# RPi.net
KiCad netlist of a schematic drawn in Altium Designer
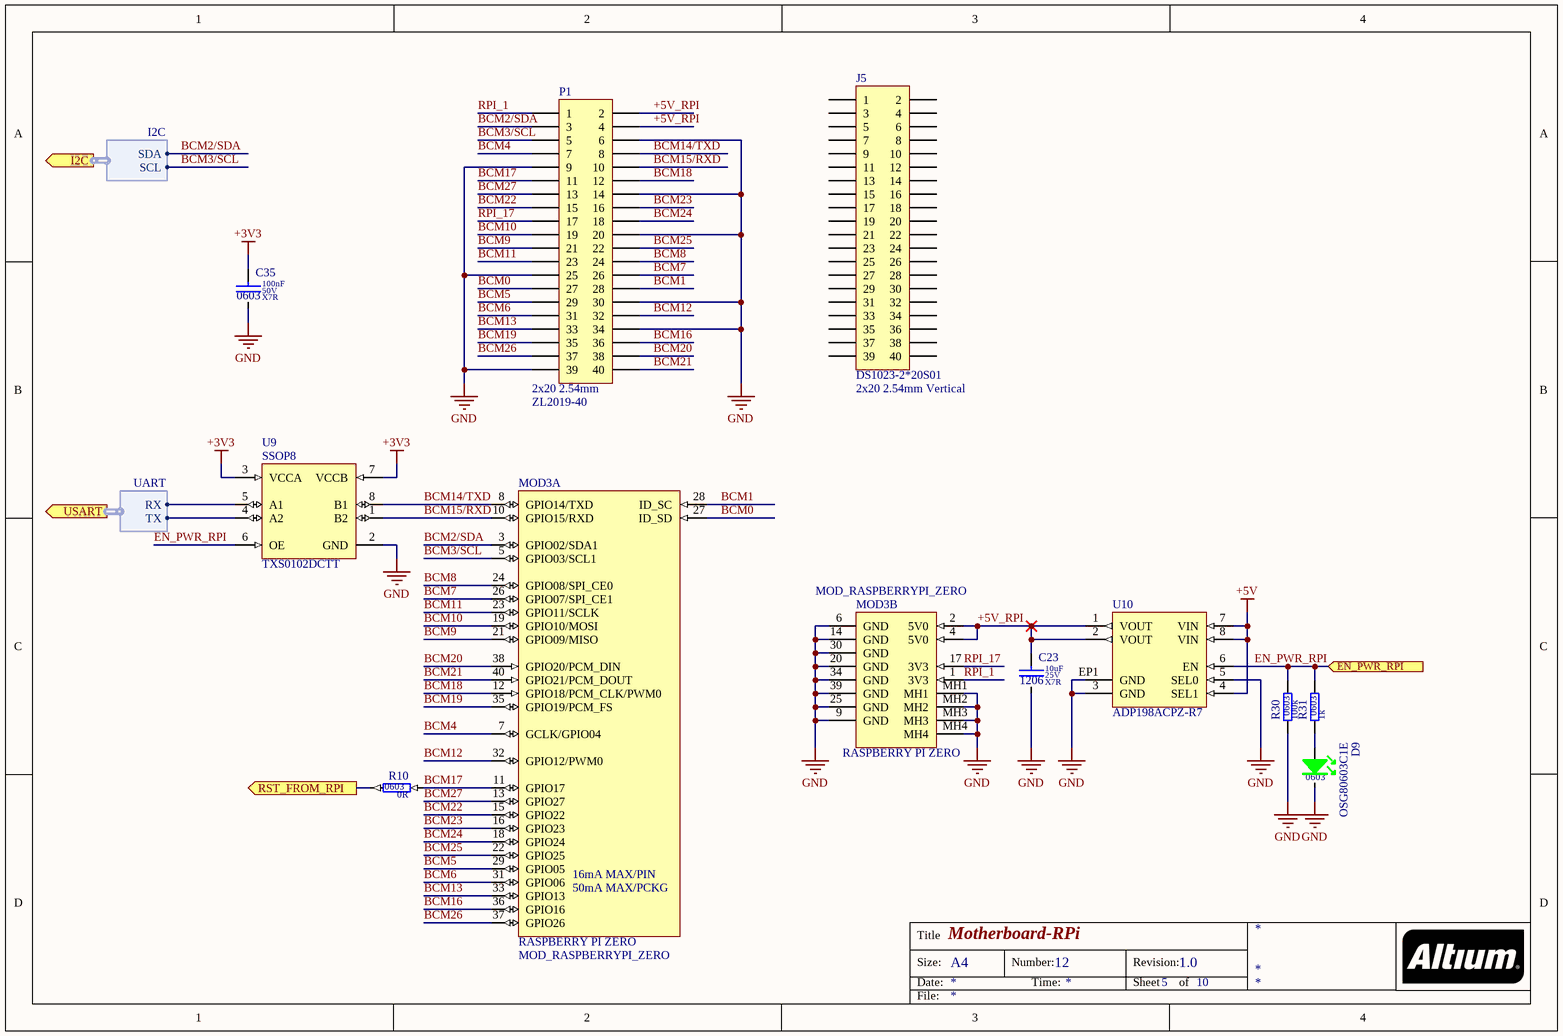
[diagram p0: RPi.SchDoc]

(export (version "E")
  (design (tool "Eeschema 10.0.6"))
  (components
    (comp (ref "C23")
      (value "10uF")
      (footprint "C_1206_3216")
      (description "Capacitor")
      (fields
        (field (name "DIELECTRIC") "X7R")
        (field (name "VOLTAGE") "25V")
        (field (name "SCH_FOOTPRINT") "1206")
        (field (name "PART NUMBER") "C_10uF_25V_X7R_1206_10")
        (field (name "MANUFACTURER") "Samsung Electro-Mechanics")
      )
      (libsource (lib "Library") (part "C"))
    )
    (comp (ref "C35")
      (value "100nF")
      (footprint "C_0603_1608")
      (description "Capacitor")
      (fields
        (field (name "DIELECTRIC") "X7R")
        (field (name "VOLTAGE") "50V")
        (field (name "SCH_FOOTPRINT") "0603")
        (field (name "PART NUMBER") "C_100nF_50V_X7R_0603_5")
        (field (name "MANUFACTURER") "Samsung")
      )
      (libsource (lib "Library") (part "C"))
    )
    (comp (ref "D9")
      (value "OSG80603C1E")
      (footprint "OL_0603_1608")
      (description "LED GREEN")
      (fields
        (field (name "SCH_FOOTPRINT") "0603")
        (field (name "PART NUMBER") "OL_G_0603_OSG80603C1E")
        (field (name "MANUFACTURER") "Optosupply")
      )
      (libsource (lib "Library") (part "OL_G"))
    )
    (comp (ref "J5")
      (value "DS1023-2*20S01")
      (footprint "J_HEADER_2x20_2.54_VERTICAL")
      (description "Pin Header")
      (fields
        (field (name "PART NUMBER") "J_HEADER_2x20_2.54_VERTICAL")
        (field (name "SCH_FOOTPRINT") "2x20 2.54mm Vertical")
        (field (name "MANUFACTURER") "Connfly")
      )
      (libsource (lib "Library") (part "J_HEADER_2x20"))
    )
    (comp (ref "MOD3")
      (value "RASPBERRY PI ZERO")
      (footprint "MOD_RASPBERRYPI_ZERO")
      (fields
        (field (name "PART NUMBER") "MOD_RASPBERRYPI_ZERO")
        (field (name "SCH_FOOTPRINT") "MOD_RASPBERRYPI_ZERO")
        (field (name "MANUFACTURER") "Raspberry Pi")
      )
      (libsource (lib "Library") (part "MOD_RASPBERRYPI_3B"))
    )
    (comp (ref "P1")
      (value "ZL2019-40")
      (footprint "P_HEADER_2x20_2.54_HIGH")
      (description "Pin Header")
      (fields
        (field (name "SCH_FOOTPRINT") "2x20 2.54mm")
        (field (name "PART NUMBER") "P_HEADER_2x20_2.54_HIGH")
        (field (name "MANUFACTURER") "Ninigi")
      )
      (libsource (lib "Library") (part "P_HEADER_2x20"))
    )
    (comp (ref "R10")
      (value "0R")
      (footprint "R_0603_1608")
      (fields
        (field (name "SCH_FOOTPRINT") "0603")
        (field (name "PART NUMBER") "R_0R_0603_5")
        (field (name "VOLTAGE") "50V")
        (field (name "POWER") "100mW")
      )
      (libsource (lib "") (part "R_1"))
    )
    (comp (ref "R30")
      (value "100k")
      (footprint "R_0603_1608")
      (fields
        (field (name "SCH_FOOTPRINT") "0603")
        (field (name "PART NUMBER") "R_100k_0603_1")
        (field (name "VOLTAGE") "50V")
        (field (name "POWER") "100mW")
      )
      (libsource (lib "Library") (part "R"))
    )
    (comp (ref "R31")
      (value "1k")
      (footprint "R_0603_1608")
      (fields
        (field (name "SCH_FOOTPRINT") "0603")
        (field (name "PART NUMBER") "R_1k_0603_1")
        (field (name "VOLTAGE") "75V")
        (field (name "POWER") "100mW")
      )
      (libsource (lib "Library") (part "R"))
    )
    (comp (ref "U9")
      (value "TXS0102DCTT")
      (footprint "SSOP8_3x3")
      (fields
        (field (name "SCH_FOOTPRINT") "SSOP8")
        (field (name "PART NUMBER") "U_TXS0102DCTT")
        (field (name "MANUFACTURER") "Texas Instruments")
      )
      (libsource (lib "Library") (part "U_TXS0102_DCT_DCU"))
    )
    (comp (ref "U10")
      (value "ADP198ACPZ-R7")
      (footprint "LFCSP-8-10")
      (fields
        (field (name "SCH_FOOTPRINT") "LFCSP8")
        (field (name "PART NUMBER") "U_ADP198ACPZ-R7")
        (field (name "MANUFACTURER") "Analog Devices")
        (field (name "Comment") "high-side load switch")
      )
      (libsource (lib "Library") (part "U_ADP198ACPZ-R7"))
    )
  )
  (nets
    (net (code "3") (name "+3V3") (class "Default")
      (node (ref "C35") (pin "1") (pinfunction "1_1") (pintype "passive"))
      (node (ref "U9") (pin "3") (pinfunction "VCCA_3") (pintype "input"))
      (node (ref "U9") (pin "7") (pinfunction "VCCB_7") (pintype "input"))
    )
    (net (code "4") (name "+5V") (class "Default")
      (node (ref "U10") (pin "4") (pinfunction "SEL1_4") (pintype "input"))
      (node (ref "U10") (pin "7") (pinfunction "VIN_7") (pintype "input"))
      (node (ref "U10") (pin "8") (pinfunction "VIN_8") (pintype "input"))
    )
    (net (code "5") (name "/+5V_RPI") (class "Default")
      (node (ref "C23") (pin "1") (pinfunction "1_1") (pintype "passive"))
      (node (ref "MOD3") (pin "2") (pinfunction "5V0_2") (pintype "input"))
      (node (ref "MOD3") (pin "4") (pinfunction "5V0_4") (pintype "input"))
      (node (ref "P1") (pin "2") (pinfunction "2_2") (pintype "passive"))
      (node (ref "P1") (pin "4") (pinfunction "4_4") (pintype "passive"))
      (node (ref "U10") (pin "1") (pinfunction "VOUT_1") (pintype "output"))
      (node (ref "U10") (pin "2") (pinfunction "VOUT_2") (pintype "output"))
    )
    (net (code "6") (name "/BCM0") (class "Default")
      (node (ref "MOD3") (pin "27") (pinfunction "ID_SD_27") (pintype "input"))
      (node (ref "P1") (pin "27") (pinfunction "27_27") (pintype "passive"))
    )
    (net (code "7") (name "/BCM1") (class "Default")
      (node (ref "MOD3") (pin "28") (pinfunction "ID_SC_28") (pintype "input"))
      (node (ref "P1") (pin "28") (pinfunction "28_28") (pintype "passive"))
    )
    (net (code "8") (name "/BCM2{slash}SDA") (class "Default")
      (node (ref "MOD3") (pin "3") (pinfunction "GPIO02/SDA1_3") (pintype "bidirectional"))
      (node (ref "P1") (pin "3") (pinfunction "3_3") (pintype "passive"))
    )
    (net (code "9") (name "/BCM3{slash}SCL") (class "Default")
      (node (ref "MOD3") (pin "5") (pinfunction "GPIO03/SCL1_5") (pintype "bidirectional"))
      (node (ref "P1") (pin "5") (pinfunction "5_5") (pintype "passive"))
    )
    (net (code "10") (name "/BCM4") (class "Default")
      (node (ref "MOD3") (pin "7") (pinfunction "GCLK/GPIO04_7") (pintype "bidirectional"))
      (node (ref "P1") (pin "7") (pinfunction "7_7") (pintype "passive"))
    )
    (net (code "11") (name "/BCM5") (class "Default")
      (node (ref "MOD3") (pin "29") (pinfunction "GPIO05_29") (pintype "bidirectional"))
      (node (ref "P1") (pin "29") (pinfunction "29_29") (pintype "passive"))
    )
    (net (code "12") (name "/BCM6") (class "Default")
      (node (ref "MOD3") (pin "31") (pinfunction "GPIO06_31") (pintype "bidirectional"))
      (node (ref "P1") (pin "31") (pinfunction "31_31") (pintype "passive"))
    )
    (net (code "13") (name "/BCM7") (class "Default")
      (node (ref "MOD3") (pin "26") (pinfunction "GPIO07/SPI_CE1_26") (pintype "bidirectional"))
      (node (ref "P1") (pin "26") (pinfunction "26_26") (pintype "passive"))
    )
    (net (code "14") (name "/BCM8") (class "Default")
      (node (ref "MOD3") (pin "24") (pinfunction "GPIO08/SPI_CE0_24") (pintype "bidirectional"))
      (node (ref "P1") (pin "24") (pinfunction "24_24") (pintype "passive"))
    )
    (net (code "15") (name "/BCM9") (class "Default")
      (node (ref "MOD3") (pin "21") (pinfunction "GPIO09/MISO_21") (pintype "bidirectional"))
      (node (ref "P1") (pin "21") (pinfunction "21_21") (pintype "passive"))
    )
    (net (code "16") (name "/BCM10") (class "Default")
      (node (ref "MOD3") (pin "19") (pinfunction "GPIO10/MOSI_19") (pintype "bidirectional"))
      (node (ref "P1") (pin "19") (pinfunction "19_19") (pintype "passive"))
    )
    (net (code "17") (name "/BCM11") (class "Default")
      (node (ref "MOD3") (pin "23") (pinfunction "GPIO11/SCLK_23") (pintype "bidirectional"))
      (node (ref "P1") (pin "23") (pinfunction "23_23") (pintype "passive"))
    )
    (net (code "18") (name "/BCM12") (class "Default")
      (node (ref "MOD3") (pin "32") (pinfunction "GPIO12/PWM0_32") (pintype "bidirectional"))
      (node (ref "P1") (pin "32") (pinfunction "32_32") (pintype "passive"))
    )
    (net (code "19") (name "/BCM13") (class "Default")
      (node (ref "MOD3") (pin "33") (pinfunction "GPIO13_33") (pintype "bidirectional"))
      (node (ref "P1") (pin "33") (pinfunction "33_33") (pintype "passive"))
    )
    (net (code "20") (name "/BCM14{slash}TXD") (class "Default")
      (node (ref "MOD3") (pin "8") (pinfunction "GPIO14/TXD_8") (pintype "bidirectional"))
      (node (ref "P1") (pin "8") (pinfunction "8_8") (pintype "passive"))
      (node (ref "U9") (pin "8") (pinfunction "B1_8") (pintype "bidirectional"))
    )
    (net (code "21") (name "/BCM15{slash}RXD") (class "Default")
      (node (ref "MOD3") (pin "10") (pinfunction "GPIO15/RXD_10") (pintype "bidirectional"))
      (node (ref "P1") (pin "10") (pinfunction "10_10") (pintype "passive"))
      (node (ref "U9") (pin "1") (pinfunction "B2_1") (pintype "bidirectional"))
    )
    (net (code "22") (name "/BCM16") (class "Default")
      (node (ref "MOD3") (pin "36") (pinfunction "GPIO16_36") (pintype "bidirectional"))
      (node (ref "P1") (pin "36") (pinfunction "36_36") (pintype "passive"))
    )
    (net (code "23") (name "/BCM17") (class "Default")
      (node (ref "MOD3") (pin "11") (pinfunction "GPIO17_11") (pintype "bidirectional"))
      (node (ref "P1") (pin "11") (pinfunction "11_11") (pintype "passive"))
      (node (ref "R10") (pin "1") (pinfunction "1_1") (pintype "input"))
    )
    (net (code "24") (name "/BCM18") (class "Default")
      (node (ref "MOD3") (pin "12") (pinfunction "GPIO18/PCM_CLK/PWM0_12") (pintype "input"))
      (node (ref "P1") (pin "12") (pinfunction "12_12") (pintype "passive"))
    )
    (net (code "25") (name "/BCM19") (class "Default")
      (node (ref "MOD3") (pin "35") (pinfunction "GPIO19/PCM_FS_35") (pintype "bidirectional"))
      (node (ref "P1") (pin "35") (pinfunction "35_35") (pintype "passive"))
    )
    (net (code "26") (name "/BCM20") (class "Default")
      (node (ref "MOD3") (pin "38") (pinfunction "GPIO20/PCM_DIN_38") (pintype "input"))
      (node (ref "P1") (pin "38") (pinfunction "38_38") (pintype "passive"))
    )
    (net (code "27") (name "/BCM21") (class "Default")
      (node (ref "MOD3") (pin "40") (pinfunction "GPIO21/PCM_DOUT_40") (pintype "input"))
      (node (ref "P1") (pin "40") (pinfunction "40_40") (pintype "passive"))
    )
    (net (code "28") (name "/BCM22") (class "Default")
      (node (ref "MOD3") (pin "15") (pinfunction "GPIO22_15") (pintype "bidirectional"))
      (node (ref "P1") (pin "15") (pinfunction "15_15") (pintype "passive"))
    )
    (net (code "29") (name "/BCM23") (class "Default")
      (node (ref "MOD3") (pin "16") (pinfunction "GPIO23_16") (pintype "bidirectional"))
      (node (ref "P1") (pin "16") (pinfunction "16_16") (pintype "passive"))
    )
    (net (code "30") (name "/BCM24") (class "Default")
      (node (ref "MOD3") (pin "18") (pinfunction "GPIO24_18") (pintype "bidirectional"))
      (node (ref "P1") (pin "18") (pinfunction "18_18") (pintype "passive"))
    )
    (net (code "31") (name "/BCM25") (class "Default")
      (node (ref "MOD3") (pin "22") (pinfunction "GPIO25_22") (pintype "bidirectional"))
      (node (ref "P1") (pin "22") (pinfunction "22_22") (pintype "passive"))
    )
    (net (code "32") (name "/BCM26") (class "Default")
      (node (ref "MOD3") (pin "37") (pinfunction "GPIO26_37") (pintype "bidirectional"))
      (node (ref "P1") (pin "37") (pinfunction "37_37") (pintype "passive"))
    )
    (net (code "33") (name "/BCM27") (class "Default")
      (node (ref "MOD3") (pin "13") (pinfunction "GPIO27_13") (pintype "bidirectional"))
      (node (ref "P1") (pin "13") (pinfunction "13_13") (pintype "passive"))
    )
    (net (code "34") (name "/EN_PWR_RPI") (class "Default")
      (node (ref "R30") (pin "2") (pinfunction "2_2") (pintype "passive"))
      (node (ref "R31") (pin "2") (pinfunction "2_2") (pintype "passive"))
      (node (ref "U10") (pin "6") (pinfunction "EN_6") (pintype "input"))
      (node (ref "U9") (pin "6") (pinfunction "OE_6") (pintype "input"))
    )
    (net (code "35") (name "/RPI_1") (class "Default")
      (node (ref "MOD3") (pin "1") (pinfunction "3V3_1") (pintype "input"))
      (node (ref "P1") (pin "1") (pinfunction "1_1") (pintype "passive"))
    )
    (net (code "36") (name "/RPI_17") (class "Default")
      (node (ref "MOD3") (pin "17") (pinfunction "3V3_17") (pintype "input"))
      (node (ref "P1") (pin "17") (pinfunction "17_17") (pintype "passive"))
    )
    (net (code "37") (name "/RST_FROM_RPI") (class "Default")
      (node (ref "R10") (pin "2") (pinfunction "2_2") (pintype "output"))
    )
    (net (code "38") (name "/RX") (class "Default")
      (node (ref "U9") (pin "5") (pinfunction "A1_5") (pintype "bidirectional"))
    )
    (net (code "39") (name "/TX") (class "Default")
      (node (ref "U9") (pin "4") (pinfunction "A2_4") (pintype "bidirectional"))
    )
    (net (code "42") (name "GND") (class "Default")
      (node (ref "C23") (pin "2") (pinfunction "2_2") (pintype "passive"))
      (node (ref "C35") (pin "2") (pinfunction "2_2") (pintype "passive"))
      (node (ref "D9") (pin "1") (pinfunction "K_1") (pintype "passive"))
      (node (ref "MOD3") (pin "14") (pinfunction "GND_14") (pintype "power_in"))
      (node (ref "MOD3") (pin "20") (pinfunction "GND_20") (pintype "power_in"))
      (node (ref "MOD3") (pin "25") (pinfunction "GND_25") (pintype "power_in"))
      (node (ref "MOD3") (pin "30") (pinfunction "GND_30") (pintype "power_in"))
      (node (ref "MOD3") (pin "34") (pinfunction "GND_34") (pintype "power_in"))
      (node (ref "MOD3") (pin "39") (pinfunction "GND_39") (pintype "power_in"))
      (node (ref "MOD3") (pin "6") (pinfunction "GND_6") (pintype "power_in"))
      (node (ref "MOD3") (pin "9") (pinfunction "GND_9") (pintype "power_in"))
      (node (ref "MOD3") (pin "MH1") (pinfunction "MH1_MH1") (pintype "passive"))
      (node (ref "MOD3") (pin "MH2") (pinfunction "MH2_MH2") (pintype "passive"))
      (node (ref "MOD3") (pin "MH3") (pinfunction "MH3_MH3") (pintype "passive"))
      (node (ref "MOD3") (pin "MH4") (pinfunction "MH4_MH4") (pintype "passive"))
      (node (ref "P1") (pin "14") (pinfunction "14_14") (pintype "passive"))
      (node (ref "P1") (pin "20") (pinfunction "20_20") (pintype "passive"))
      (node (ref "P1") (pin "25") (pinfunction "25_25") (pintype "passive"))
      (node (ref "P1") (pin "30") (pinfunction "30_30") (pintype "passive"))
      (node (ref "P1") (pin "34") (pinfunction "34_34") (pintype "passive"))
      (node (ref "P1") (pin "39") (pinfunction "39_39") (pintype "passive"))
      (node (ref "P1") (pin "6") (pinfunction "6_6") (pintype "passive"))
      (node (ref "P1") (pin "9") (pinfunction "9_9") (pintype "passive"))
      (node (ref "R30") (pin "1") (pinfunction "1_1") (pintype "passive"))
      (node (ref "U10") (pin "3") (pinfunction "GND_3") (pintype "power_in"))
      (node (ref "U10") (pin "5") (pinfunction "SEL0_5") (pintype "input"))
      (node (ref "U10") (pin "EP1") (pinfunction "GND_EP1") (pintype "power_in"))
      (node (ref "U9") (pin "2") (pinfunction "GND_2") (pintype "power_in"))
    )
    (net (code "43") (name "Net-(D9-A)") (class "Default")
      (node (ref "D9") (pin "2") (pinfunction "A_2") (pintype "passive"))
      (node (ref "R31") (pin "1") (pinfunction "1_1") (pintype "passive"))
    )
    (net (code "44") (name "unconnected-(J5-Pad1)") (class "Default")
      (node (ref "J5") (pin "1") (pinfunction "1_1") (pintype "passive"))
    )
    (net (code "45") (name "unconnected-(J5-Pad2)") (class "Default")
      (node (ref "J5") (pin "2") (pinfunction "2_2") (pintype "passive"))
    )
    (net (code "46") (name "unconnected-(J5-Pad3)") (class "Default")
      (node (ref "J5") (pin "3") (pinfunction "3_3") (pintype "passive"))
    )
    (net (code "47") (name "unconnected-(J5-Pad4)") (class "Default")
      (node (ref "J5") (pin "4") (pinfunction "4_4") (pintype "passive"))
    )
    (net (code "48") (name "unconnected-(J5-Pad5)") (class "Default")
      (node (ref "J5") (pin "5") (pinfunction "5_5") (pintype "passive"))
    )
    (net (code "49") (name "unconnected-(J5-Pad6)") (class "Default")
      (node (ref "J5") (pin "6") (pinfunction "6_6") (pintype "passive"))
    )
    (net (code "50") (name "unconnected-(J5-Pad7)") (class "Default")
      (node (ref "J5") (pin "7") (pinfunction "7_7") (pintype "passive"))
    )
    (net (code "51") (name "unconnected-(J5-Pad8)") (class "Default")
      (node (ref "J5") (pin "8") (pinfunction "8_8") (pintype "passive"))
    )
    (net (code "52") (name "unconnected-(J5-Pad9)") (class "Default")
      (node (ref "J5") (pin "9") (pinfunction "9_9") (pintype "passive"))
    )
    (net (code "53") (name "unconnected-(J5-Pad10)") (class "Default")
      (node (ref "J5") (pin "10") (pinfunction "10_10") (pintype "passive"))
    )
    (net (code "54") (name "unconnected-(J5-Pad11)") (class "Default")
      (node (ref "J5") (pin "11") (pinfunction "11_11") (pintype "passive"))
    )
    (net (code "55") (name "unconnected-(J5-Pad12)") (class "Default")
      (node (ref "J5") (pin "12") (pinfunction "12_12") (pintype "passive"))
    )
    (net (code "56") (name "unconnected-(J5-Pad13)") (class "Default")
      (node (ref "J5") (pin "13") (pinfunction "13_13") (pintype "passive"))
    )
    (net (code "57") (name "unconnected-(J5-Pad14)") (class "Default")
      (node (ref "J5") (pin "14") (pinfunction "14_14") (pintype "passive"))
    )
    (net (code "58") (name "unconnected-(J5-Pad15)") (class "Default")
      (node (ref "J5") (pin "15") (pinfunction "15_15") (pintype "passive"))
    )
    (net (code "59") (name "unconnected-(J5-Pad16)") (class "Default")
      (node (ref "J5") (pin "16") (pinfunction "16_16") (pintype "passive"))
    )
    (net (code "60") (name "unconnected-(J5-Pad17)") (class "Default")
      (node (ref "J5") (pin "17") (pinfunction "17_17") (pintype "passive"))
    )
    (net (code "61") (name "unconnected-(J5-Pad18)") (class "Default")
      (node (ref "J5") (pin "18") (pinfunction "18_18") (pintype "passive"))
    )
    (net (code "62") (name "unconnected-(J5-Pad19)") (class "Default")
      (node (ref "J5") (pin "19") (pinfunction "19_19") (pintype "passive"))
    )
    (net (code "63") (name "unconnected-(J5-Pad20)") (class "Default")
      (node (ref "J5") (pin "20") (pinfunction "20_20") (pintype "passive"))
    )
    (net (code "64") (name "unconnected-(J5-Pad21)") (class "Default")
      (node (ref "J5") (pin "21") (pinfunction "21_21") (pintype "passive"))
    )
    (net (code "65") (name "unconnected-(J5-Pad22)") (class "Default")
      (node (ref "J5") (pin "22") (pinfunction "22_22") (pintype "passive"))
    )
    (net (code "66") (name "unconnected-(J5-Pad23)") (class "Default")
      (node (ref "J5") (pin "23") (pinfunction "23_23") (pintype "passive"))
    )
    (net (code "67") (name "unconnected-(J5-Pad24)") (class "Default")
      (node (ref "J5") (pin "24") (pinfunction "24_24") (pintype "passive"))
    )
    (net (code "68") (name "unconnected-(J5-Pad25)") (class "Default")
      (node (ref "J5") (pin "25") (pinfunction "25_25") (pintype "passive"))
    )
    (net (code "69") (name "unconnected-(J5-Pad26)") (class "Default")
      (node (ref "J5") (pin "26") (pinfunction "26_26") (pintype "passive"))
    )
    (net (code "70") (name "unconnected-(J5-Pad27)") (class "Default")
      (node (ref "J5") (pin "27") (pinfunction "27_27") (pintype "passive"))
    )
    (net (code "71") (name "unconnected-(J5-Pad28)") (class "Default")
      (node (ref "J5") (pin "28") (pinfunction "28_28") (pintype "passive"))
    )
    (net (code "72") (name "unconnected-(J5-Pad29)") (class "Default")
      (node (ref "J5") (pin "29") (pinfunction "29_29") (pintype "passive"))
    )
    (net (code "73") (name "unconnected-(J5-Pad30)") (class "Default")
      (node (ref "J5") (pin "30") (pinfunction "30_30") (pintype "passive"))
    )
    (net (code "74") (name "unconnected-(J5-Pad31)") (class "Default")
      (node (ref "J5") (pin "31") (pinfunction "31_31") (pintype "passive"))
    )
    (net (code "75") (name "unconnected-(J5-Pad32)") (class "Default")
      (node (ref "J5") (pin "32") (pinfunction "32_32") (pintype "passive"))
    )
    (net (code "76") (name "unconnected-(J5-Pad33)") (class "Default")
      (node (ref "J5") (pin "33") (pinfunction "33_33") (pintype "passive"))
    )
    (net (code "77") (name "unconnected-(J5-Pad34)") (class "Default")
      (node (ref "J5") (pin "34") (pinfunction "34_34") (pintype "passive"))
    )
    (net (code "78") (name "unconnected-(J5-Pad35)") (class "Default")
      (node (ref "J5") (pin "35") (pinfunction "35_35") (pintype "passive"))
    )
    (net (code "79") (name "unconnected-(J5-Pad36)") (class "Default")
      (node (ref "J5") (pin "36") (pinfunction "36_36") (pintype "passive"))
    )
    (net (code "80") (name "unconnected-(J5-Pad37)") (class "Default")
      (node (ref "J5") (pin "37") (pinfunction "37_37") (pintype "passive"))
    )
    (net (code "81") (name "unconnected-(J5-Pad38)") (class "Default")
      (node (ref "J5") (pin "38") (pinfunction "38_38") (pintype "passive"))
    )
    (net (code "82") (name "unconnected-(J5-Pad39)") (class "Default")
      (node (ref "J5") (pin "39") (pinfunction "39_39") (pintype "passive"))
    )
    (net (code "83") (name "unconnected-(J5-Pad40)") (class "Default")
      (node (ref "J5") (pin "40") (pinfunction "40_40") (pintype "passive"))
    )
  )
)
